# Works_005.net
KiCad netlist of a schematic drawn in EAGLE
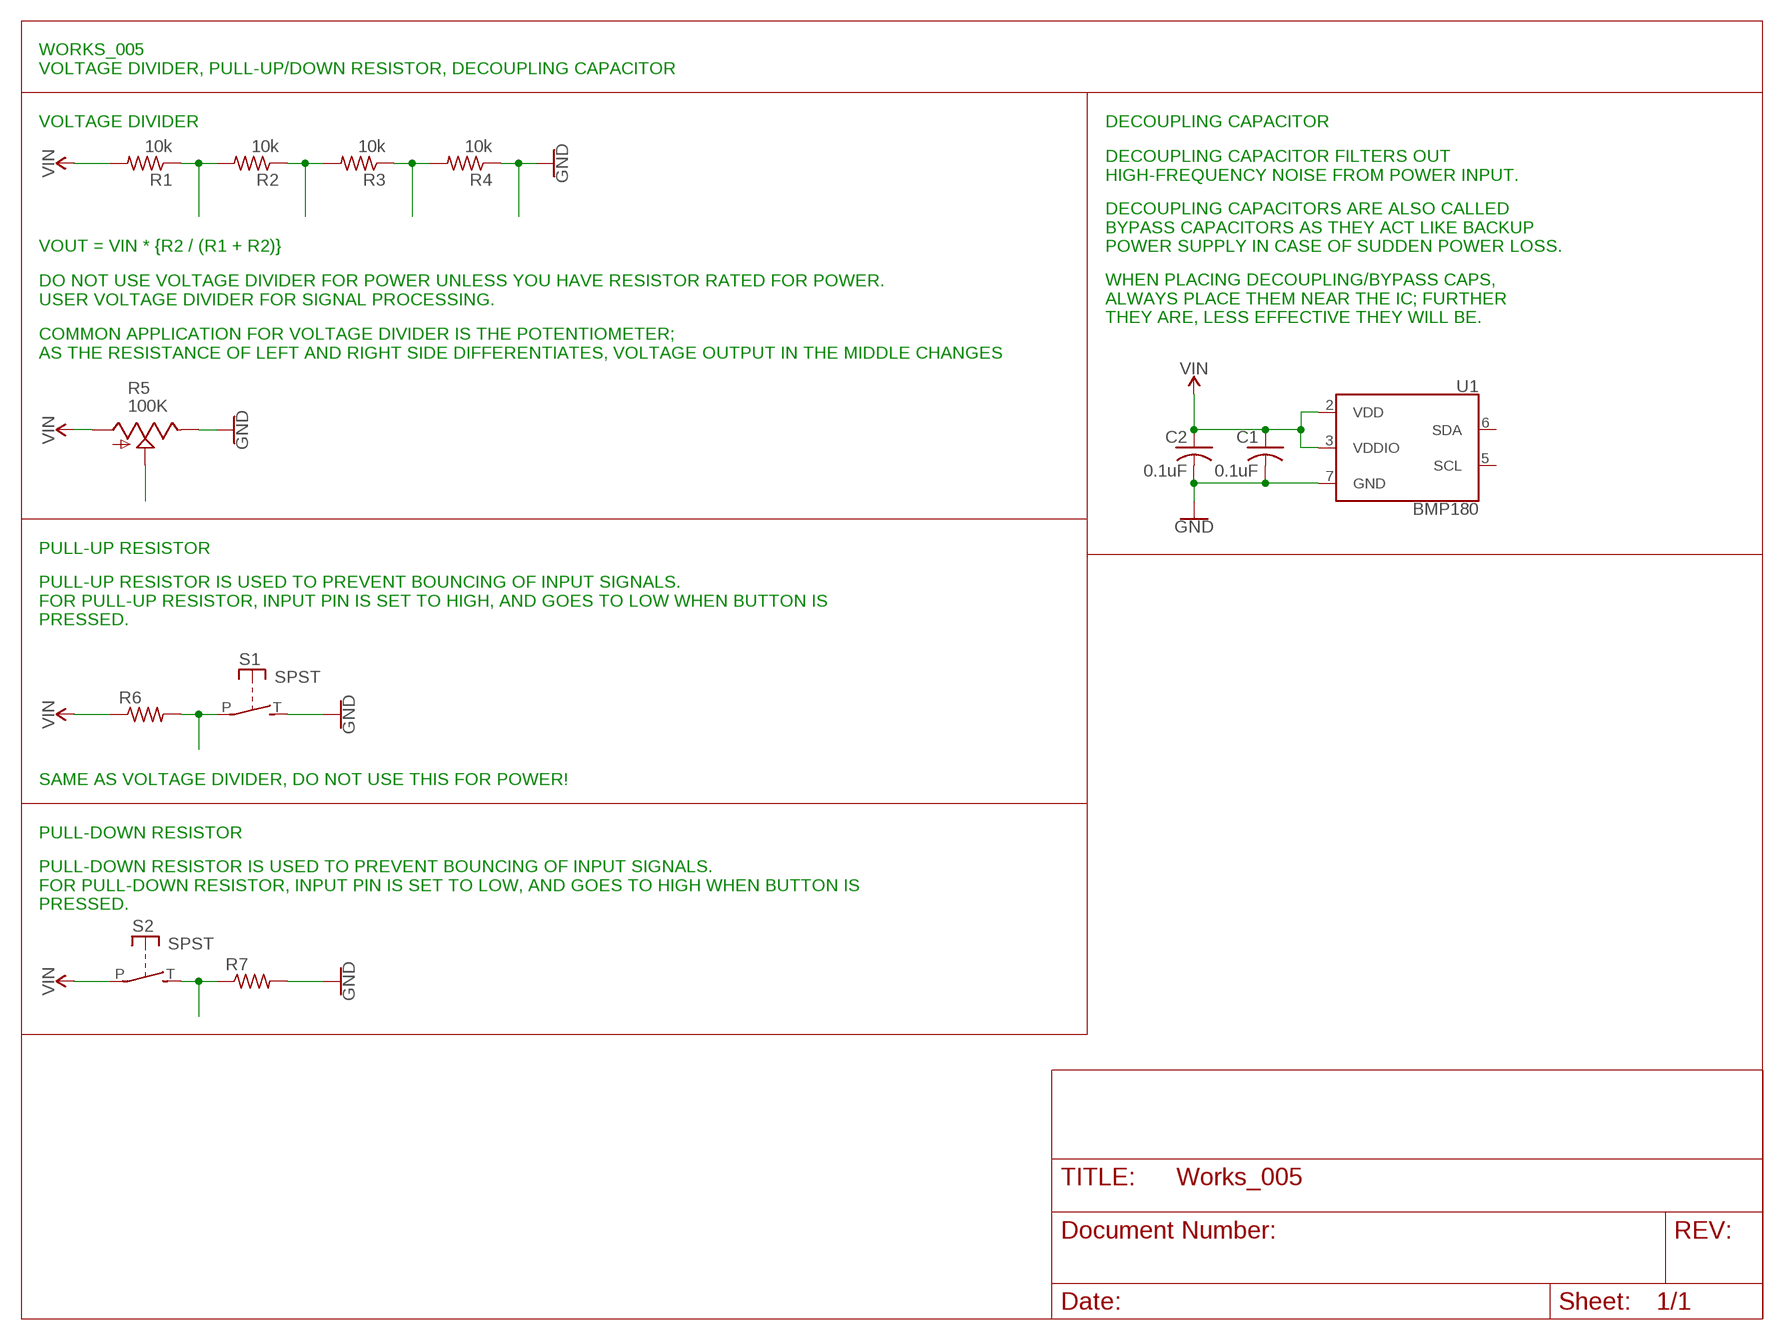
[diagram p0: schematic, sheet 1]

(export (version "E")
  (design (tool "Eeschema 10.0.6"))
  (components
    (comp (ref "C1")
      (value "0.1uF")
      (footprint "eagle-import:C0805")
      (libsource (lib "eagle-import") (part "C-USC0805"))
    )
    (comp (ref "C2")
      (value "0.1uF")
      (footprint "eagle-import:C0805")
      (libsource (lib "eagle-import") (part "C-USC0805"))
    )
    (comp (ref "R1")
      (value "10k")
      (footprint "eagle-import:R0805")
      (libsource (lib "eagle-import") (part "R-US_R0805"))
    )
    (comp (ref "R2")
      (value "10k")
      (footprint "eagle-import:R0805")
      (libsource (lib "eagle-import") (part "R-US_R0805"))
    )
    (comp (ref "R3")
      (value "10k")
      (footprint "eagle-import:R0805")
      (libsource (lib "eagle-import") (part "R-US_R0805"))
    )
    (comp (ref "R4")
      (value "10k")
      (footprint "eagle-import:R0805")
      (libsource (lib "eagle-import") (part "R-US_R0805"))
    )
    (comp (ref "R5")
      (value "100K")
      (footprint "eagle-import:ST10")
      (libsource (lib "eagle-import") (part "TRIM_US-ST10"))
    )
    (comp (ref "R6")
      (value "R-US_R0805")
      (footprint "eagle-import:R0805")
      (libsource (lib "eagle-import") (part "R-US_R0805"))
    )
    (comp (ref "R7")
      (value "R-US_R0805")
      (footprint "eagle-import:R0805")
      (libsource (lib "eagle-import") (part "R-US_R0805"))
    )
    (comp (ref "S1")
      (value "SPST")
      (footprint "eagle-import:JUDCOSPST")
      (libsource (lib "eagle-import") (part "SPST"))
    )
    (comp (ref "S2")
      (value "SPST")
      (footprint "eagle-import:JUDCOSPST")
      (libsource (lib "eagle-import") (part "SPST"))
    )
    (comp (ref "U1")
      (value "BMP180")
      (footprint "eagle-import:BMP180")
      (libsource (lib "eagle-import") (part "BMP180"))
    )
  )
  (nets
    (net (code "1") (name "GND") (class "Default")
      (node (ref "C1") (pin "2") (pinfunction "2_2") (pintype "passive"))
      (node (ref "C2") (pin "2") (pinfunction "2_2") (pintype "passive"))
      (node (ref "R4") (pin "1") (pinfunction "1_1") (pintype "passive"))
      (node (ref "R5") (pin "E") (pinfunction "E_E") (pintype "passive"))
      (node (ref "R7") (pin "2") (pinfunction "2_2") (pintype "passive"))
      (node (ref "S1") (pin "T") (pinfunction "S_T") (pintype "passive"))
      (node (ref "U1") (pin "7") (pinfunction "GND_7") (pintype "power_in"))
    )
    (net (code "2") (name "Net-(R1-Pad1)") (class "Default")
      (node (ref "R1") (pin "1") (pinfunction "1_1") (pintype "passive"))
      (node (ref "R2") (pin "2") (pinfunction "2_2") (pintype "passive"))
    )
    (net (code "3") (name "Net-(R2-Pad1)") (class "Default")
      (node (ref "R2") (pin "1") (pinfunction "1_1") (pintype "passive"))
      (node (ref "R3") (pin "2") (pinfunction "2_2") (pintype "passive"))
    )
    (net (code "4") (name "Net-(R3-Pad1)") (class "Default")
      (node (ref "R3") (pin "1") (pinfunction "1_1") (pintype "passive"))
      (node (ref "R4") (pin "2") (pinfunction "2_2") (pintype "passive"))
    )
    (net (code "5") (name "Net-(R6-Pad2)") (class "Default")
      (node (ref "R6") (pin "2") (pinfunction "2_2") (pintype "passive"))
      (node (ref "S1") (pin "P") (pinfunction "P_P") (pintype "passive"))
    )
    (net (code "6") (name "Net-(S2-S)") (class "Default")
      (node (ref "R7") (pin "1") (pinfunction "1_1") (pintype "passive"))
      (node (ref "S2") (pin "T") (pinfunction "S_T") (pintype "passive"))
    )
    (net (code "7") (name "VIN") (class "Default")
      (node (ref "C1") (pin "1") (pinfunction "1_1") (pintype "passive"))
      (node (ref "C2") (pin "1") (pinfunction "1_1") (pintype "passive"))
      (node (ref "R1") (pin "2") (pinfunction "2_2") (pintype "passive"))
      (node (ref "R5") (pin "A") (pinfunction "A_A") (pintype "passive"))
      (node (ref "R6") (pin "1") (pinfunction "1_1") (pintype "passive"))
      (node (ref "S2") (pin "P") (pinfunction "P_P") (pintype "passive"))
      (node (ref "U1") (pin "2") (pinfunction "VDD_2") (pintype "power_in"))
      (node (ref "U1") (pin "3") (pinfunction "VDDIO_3") (pintype "power_in"))
    )
    (net (code "8") (name "unconnected-(R5-PadS)") (class "Default")
      (node (ref "R5") (pin "S") (pinfunction "S_S") (pintype "passive"))
    )
    (net (code "9") (name "unconnected-(U1-SCL-Pad5)") (class "Default")
      (node (ref "U1") (pin "5") (pinfunction "SCL_5") (pintype "input"))
    )
    (net (code "10") (name "unconnected-(U1-SDA-Pad6)") (class "Default")
      (node (ref "U1") (pin "6") (pinfunction "SDA_6") (pintype "bidirectional"))
    )
  )
)
